# Discharge_Board_rev1.net
KiCad netlist of a schematic drawn in EAGLE
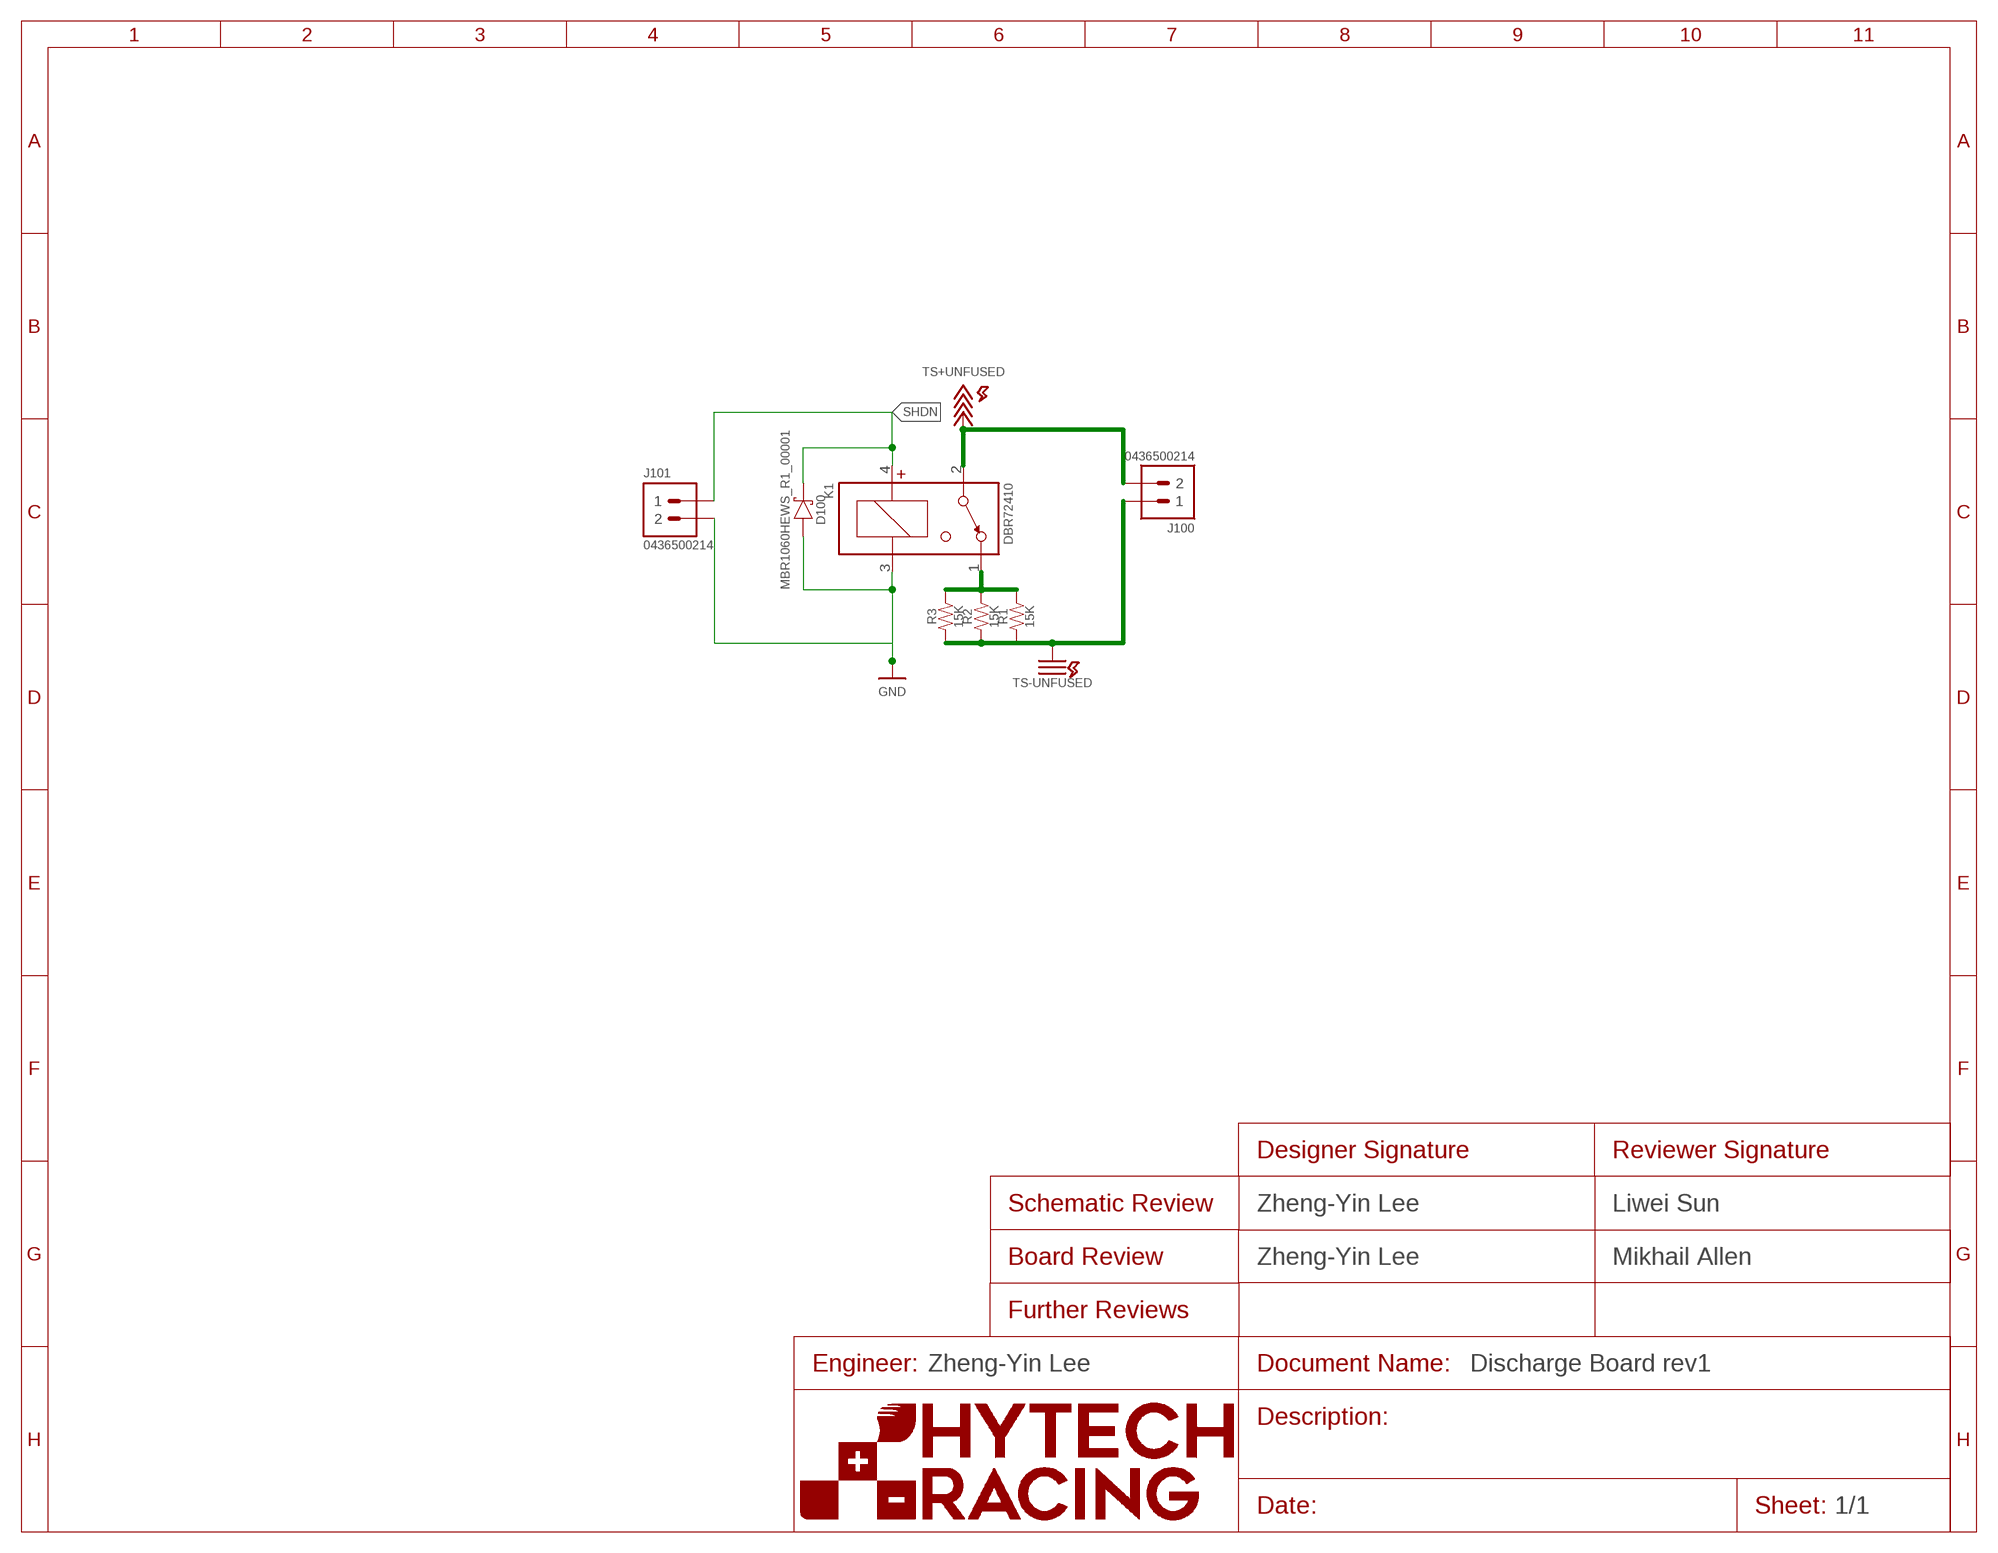
[diagram p0: schematic, sheet 1]

(export (version "E")
  (design (tool "Eeschema 10.0.6"))
  (components
    (comp (ref "D100")
      (value "SCHOTTKY_SOD323_60V")
      (footprint "eagle-import:SOD-323")
      (fields
        (field (name "MANUFACTURER") "Panjit International Inc.")
        (field (name "MPN") "MBR1060HEWS_R1_00001")
        (field (name "VOLTAGE") "60V")
      )
      (libsource (lib "eagle-import") (part "SCHOTTKY_?_SOD32360V"))
    )
    (comp (ref "J100")
      (value "CONNECTOR-2_MICROFIT_SMD_RIGHTANGLE_02_SINGLE_BLACK")
      (footprint "eagle-import:MOLEX_MICROFIT_SMD_RIGHTANGLE_02_SINGLE")
      (fields (field (name "MANUFACTURER") "Molex") (field (name "MPN") "0436500214"))
      (libsource (lib "eagle-import") (part "CONNECTOR-2_?_MICROFIT_SMD_RIGHTANGLE_02_SINGLEBLACK"))
    )
    (comp (ref "J101")
      (value "CONNECTOR-2_MICROFIT_SMD_RIGHTANGLE_02_SINGLE_BLACK")
      (footprint "eagle-import:MOLEX_MICROFIT_SMD_RIGHTANGLE_02_SINGLE")
      (fields (field (name "MANUFACTURER") "Molex") (field (name "MPN") "0436500214"))
      (libsource (lib "eagle-import") (part "CONNECTOR-2_?_MICROFIT_SMD_RIGHTANGLE_02_SINGLEBLACK"))
    )
    (comp (ref "K1")
      (value "RELAY_SPST_NC_POLARIZED_D_24")
      (footprint "eagle-import:D")
      (fields (field (name "MANUFACTURER") "Sensata-Cynergy3") (field (name "MPN") "DBR72410"))
      (libsource (lib "eagle-import") (part "RELAY_SPST_NC_POLARIZED_?D_24"))
    )
    (comp (ref "R1")
      (value "RESISTOR_B20-SHORTENED_15K")
      (footprint "eagle-import:B20-SHORTENED")
      (fields
        (field (name "MANUFACTURER") "Ohmite")
        (field (name "MPN") "B20J15KE")
        (field (name "POWER") "20W")
        (field (name "RESISTANCE") "15K")
      )
      (libsource (lib "eagle-import") (part "RESISTOR_?_B20-SHORTENED15K"))
    )
    (comp (ref "R2")
      (value "RESISTOR_B20-SHORTENED_15K")
      (footprint "eagle-import:B20-SHORTENED")
      (fields
        (field (name "MANUFACTURER") "Ohmite")
        (field (name "MPN") "B20J15KE")
        (field (name "POWER") "20W")
        (field (name "RESISTANCE") "15K")
      )
      (libsource (lib "eagle-import") (part "RESISTOR_?_B20-SHORTENED15K"))
    )
    (comp (ref "R3")
      (value "RESISTOR_B20-SHORTENED_15K")
      (footprint "eagle-import:B20-SHORTENED")
      (fields
        (field (name "MANUFACTURER") "Ohmite")
        (field (name "MPN") "B20J15KE")
        (field (name "POWER") "20W")
        (field (name "RESISTANCE") "15K")
      )
      (libsource (lib "eagle-import") (part "RESISTOR_?_B20-SHORTENED15K"))
    )
  )
  (nets
    (net (code "1") (name "GND") (class "Default")
      (node (ref "D100") (pin "A") (pinfunction "A_A") (pintype "passive"))
      (node (ref "J101") (pin "2") (pinfunction "2_2") (pintype "passive"))
      (node (ref "K1") (pin "3") (pinfunction "COIL-_3") (pintype "bidirectional"))
    )
    (net (code "2") (name "Net-(K1-CONTACT2)") (class "Default")
      (node (ref "K1") (pin "1") (pinfunction "CONTACT2_1") (pintype "bidirectional"))
      (node (ref "R1") (pin "2") (pinfunction "2_2") (pintype "passive"))
      (node (ref "R2") (pin "2") (pinfunction "2_2") (pintype "passive"))
      (node (ref "R3") (pin "2") (pinfunction "2_2") (pintype "passive"))
    )
    (net (code "3") (name "SHDN") (class "Default")
      (node (ref "D100") (pin "C") (pinfunction "C_C") (pintype "passive"))
      (node (ref "J101") (pin "1") (pinfunction "1_1") (pintype "passive"))
      (node (ref "K1") (pin "4") (pinfunction "COIL+_4") (pintype "bidirectional"))
    )
    (net (code "4") (name "TS+UNFUSED") (class "Default")
      (node (ref "J100") (pin "2") (pinfunction "2_2") (pintype "passive"))
      (node (ref "K1") (pin "2") (pinfunction "CONTACT1_2") (pintype "bidirectional"))
    )
    (net (code "5") (name "TS-UNFUSED") (class "Default")
      (node (ref "J100") (pin "1") (pinfunction "1_1") (pintype "passive"))
      (node (ref "R1") (pin "1") (pinfunction "1_1") (pintype "passive"))
      (node (ref "R2") (pin "1") (pinfunction "1_1") (pintype "passive"))
      (node (ref "R3") (pin "1") (pinfunction "1_1") (pintype "passive"))
    )
  )
)
